# Shield_V4_Connector_test_only.net
KiCad netlist of a schematic drawn in EasyEDA
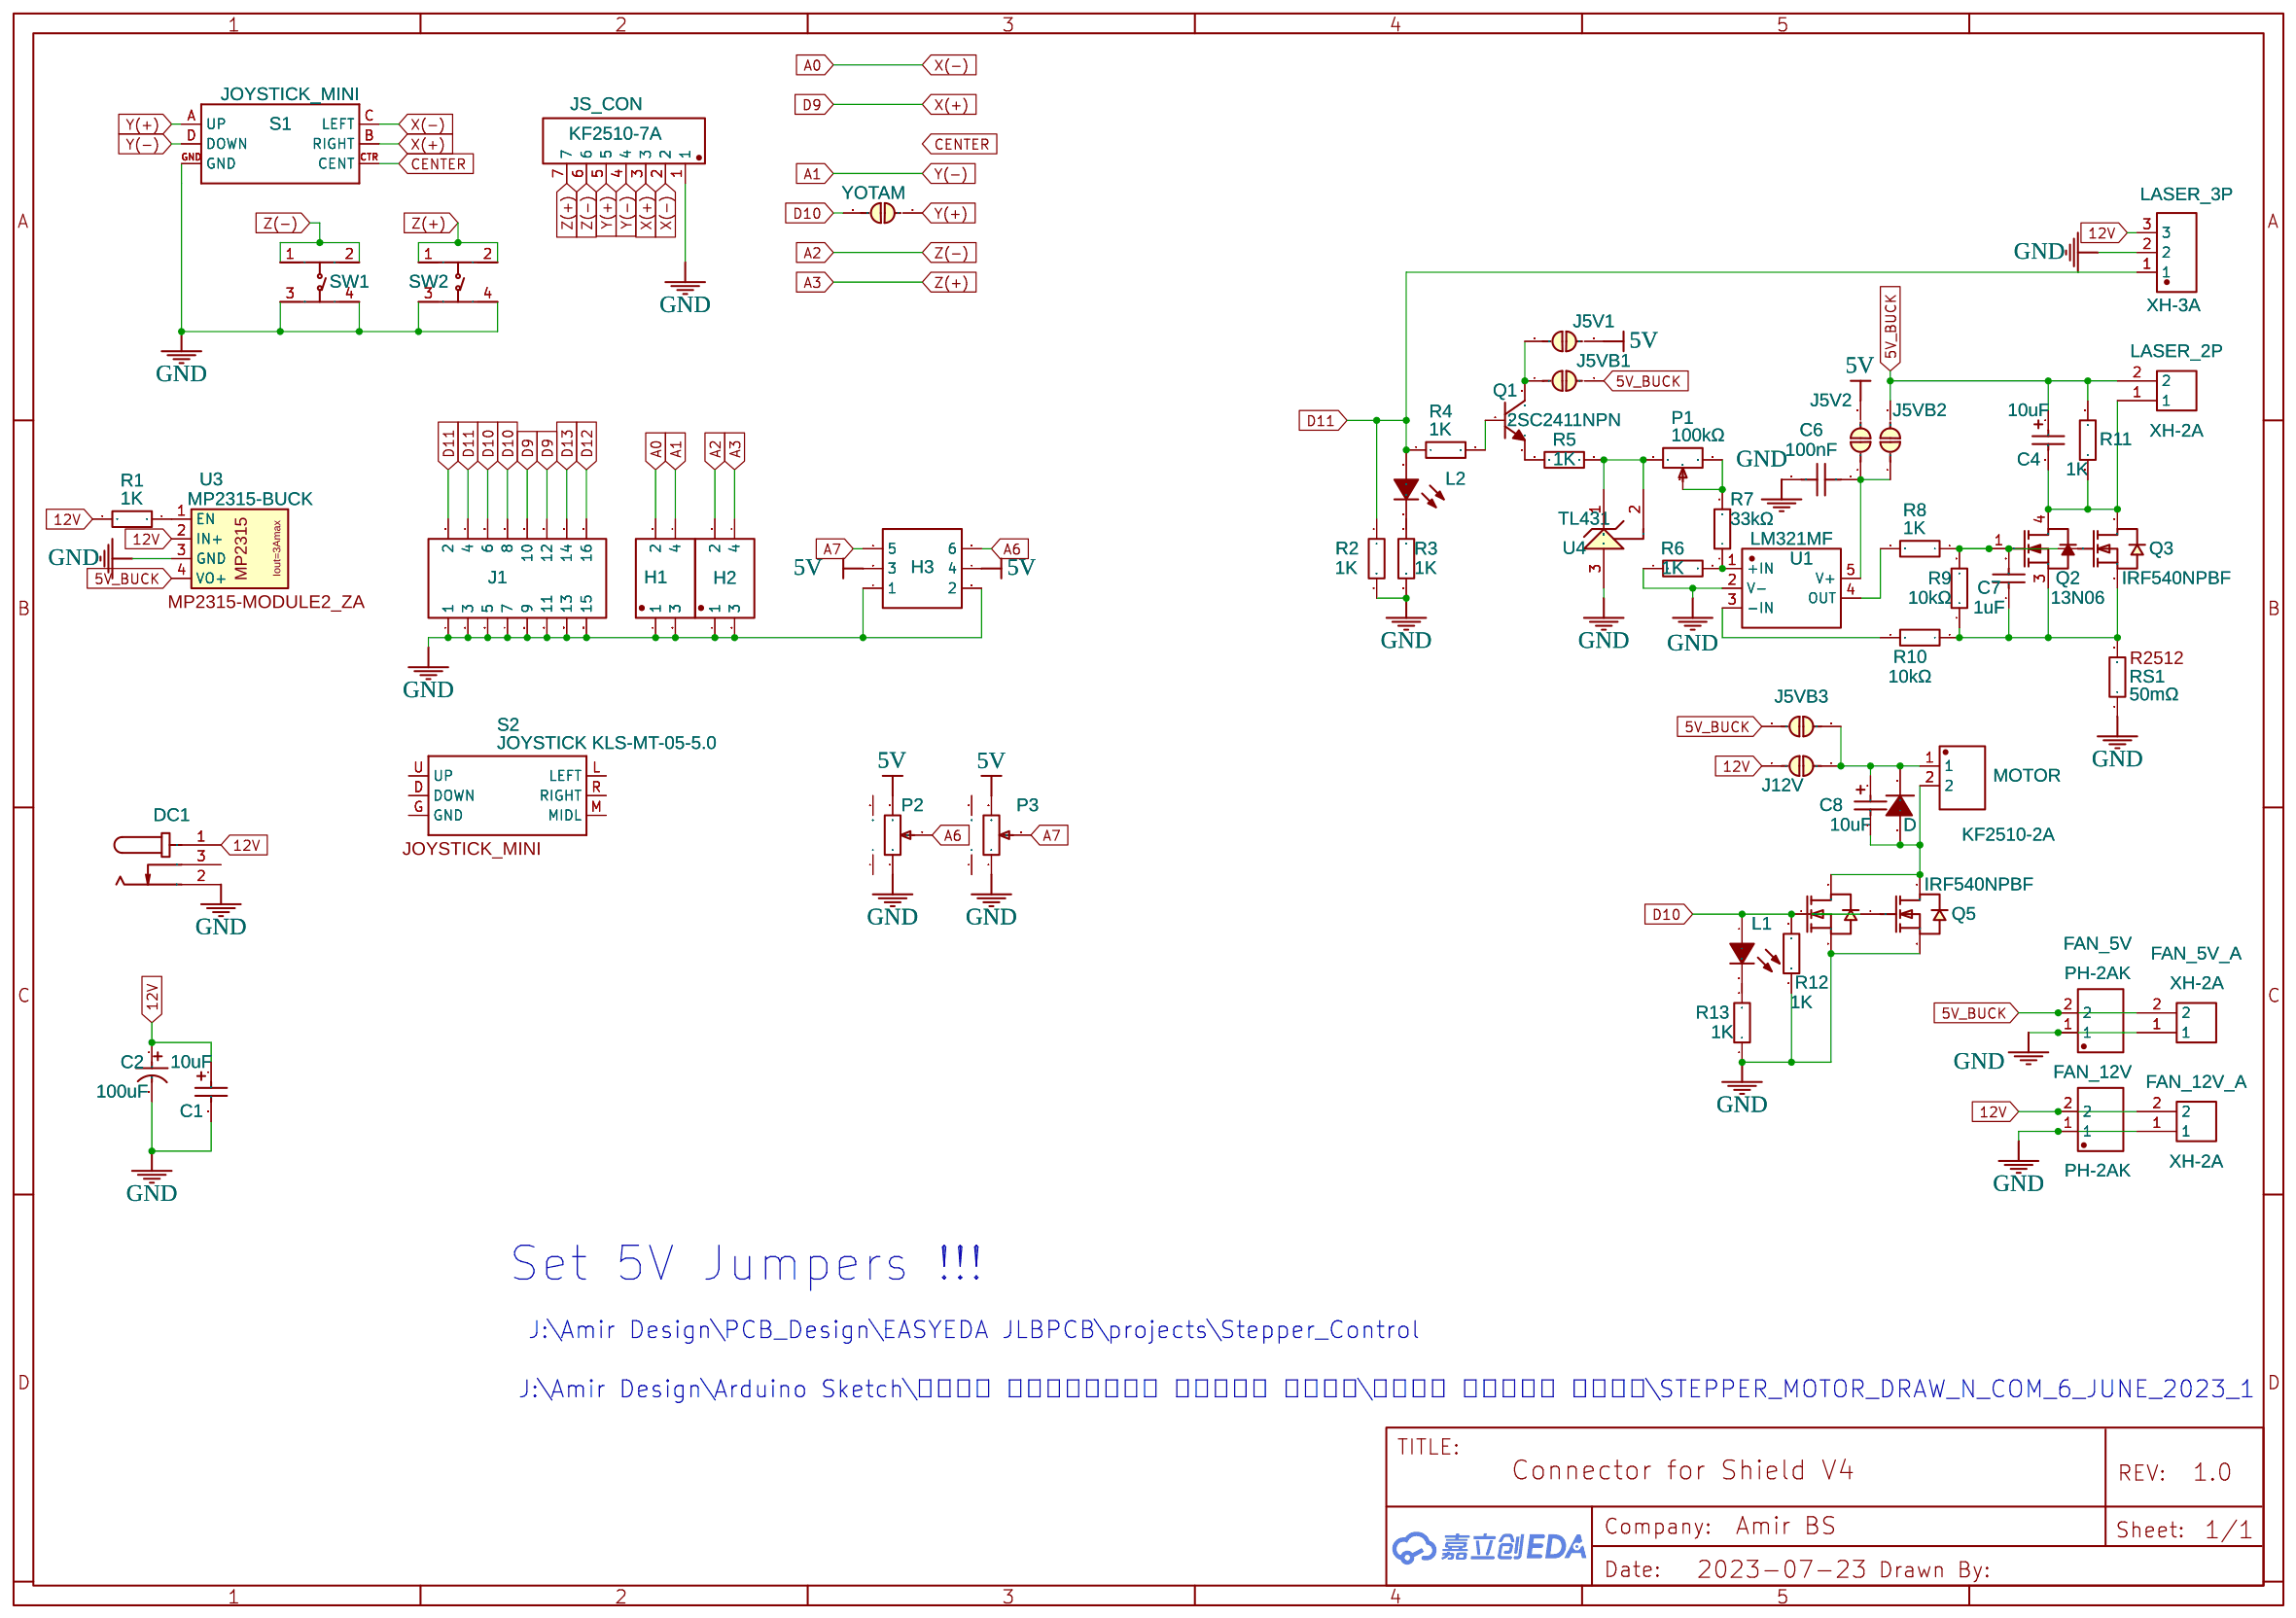
[diagram p0: schematic sheet]

(export (version "E")
  (design (tool "Eeschema 10.0.6"))
  (components
    (comp (ref "C1")
      (value "10uF")
      (fields (field (name "Manufacturer Part") "TAJA106K016RNJ") (field (name "Manufacturer") "Kyocera AVX"))
      (libsource (lib "") (part "TAJA106K016RNJ"))
    )
    (comp (ref "C2")
      (value "100uF")
      (fields
        (field (name "Manufacturer Part") "KM107M035E11RR0VH2FP0")
        (field (name "Manufacturer") "CX(承兴)")
      )
      (libsource (lib "") (part "100uF 35V 6.3*11"))
    )
    (comp (ref "C4")
      (value "10uF")
      (fields (field (name "Manufacturer Part") "TAJA106K016RNJ") (field (name "Manufacturer") "Kyocera AVX"))
      (libsource (lib "") (part "TAJA106K016RNJ"))
    )
    (comp (ref "C6")
      (value "100nF")
      (fields
        (field (name "BOM_Manufacturer Part") "CC0603KRX7R9BB104")
        (field (name "BOM_Supplier Part") "C14663")
      )
      (libsource (lib "") (part "CC0603KRX7R9BB104"))
    )
    (comp (ref "C7")
      (value "1uF")
      (fields
        (field (name "Manufacturer Part") "CL10A105KB8NNNC")
        (field (name "Manufacturer") "SAMSUNG(三星)")
      )
      (libsource (lib "") (part "CL10A105KB8NNNC"))
    )
    (comp (ref "C8")
      (value "10uF")
      (fields (field (name "Manufacturer Part") "TAJA106K016RNJ") (field (name "Manufacturer") "Kyocera AVX"))
      (libsource (lib "") (part "TAJA106K016RNJ"))
    )
    (comp (ref "D")
      (value "1N4007")
      (fields (field (name "BOM_Manufacturer Part") "1N4007F") (field (name "BOM_Supplier Part") "C110856"))
      (libsource (lib "") (part "1N4007F"))
    )
    (comp (ref "DC1")
      (value "DC")
      (fields
        (field (name "BOM_Manufacturer Part") "DC005-2.0MM")
        (field (name "BOM_Supplier Part") "C111567")
      )
      (libsource (lib "") (part "DC005-2.0MM"))
    )
    (comp (ref "FAN_5V")
      (value "PH-2AK")
      (fields (field (name "BOM_Supplier Part") "C8886"))
      (libsource (lib "") (part "PH-2AK"))
    )
    (comp (ref "FAN_5V_A")
      (value "XH-2A")
      (fields (field (name "Manufacturer") "BOOMELE(博穆精密)"))
      (libsource (lib "") (part "XH-2A_1"))
    )
    (comp (ref "FAN_12V")
      (value "PH-2AK")
      (fields (field (name "BOM_Supplier Part") "C8886"))
      (libsource (lib "") (part "PH-2AK_1"))
    )
    (comp (ref "FAN_12V_A")
      (value "XH-2A")
      (fields (field (name "Manufacturer") "BOOMELE(博穆精密)"))
      (libsource (lib "") (part "XH-2A"))
    )
    (comp (ref "H1")
      (value "Header-Female-2.54_2x2")
      (fields
        (field (name "BOM_Manufacturer Part") "DS1023-2*2SF11")
        (field (name "BOM_Supplier Part") "C92273")
      )
      (libsource (lib "") (part "Header-Female-2.54_2x2"))
    )
    (comp (ref "H2")
      (value "Header-Female-2.54_2x2")
      (fields
        (field (name "BOM_Manufacturer Part") "DS1023-2*2SF11")
        (field (name "BOM_Supplier Part") "C92273")
      )
      (libsource (lib "") (part "Header-Female-2.54_2x2"))
    )
    (comp (ref "H3")
      (value "Header-Female-2.54_2x3")
      (fields
        (field (name "BOM_Manufacturer Part") "DS1023-2*3SF11")
        (field (name "BOM_Supplier Part") "C92272")
      )
      (libsource (lib "") (part "Header-Female-2.54_2x3"))
    )
    (comp (ref "J1")
      (value "Header-Female-2.54_2x8")
      (fields (field (name "BOM_Manufacturer Part") "2.54-2*8P母") (field (name "BOM_Supplier Part") "C30734"))
      (libsource (lib "") (part "Header-Female-2.54_2x8"))
    )
    (comp (ref "J5V1") (value "JUMPER-SMT_2") (libsource (lib "") (part "JUMPER-SMT_2_2")))
    (comp (ref "J5V2") (value "JUMPER-SMT_2") (libsource (lib "") (part "JUMPER-SMT_2_5")))
    (comp (ref "J5VB1") (value "JUMPER-SMT_2") (libsource (lib "") (part "JUMPER-SMT_2_6")))
    (comp (ref "J5VB2") (value "JUMPER-SMT_2") (libsource (lib "") (part "JUMPER-SMT_2")))
    (comp (ref "J5VB3") (value "JUMPER-SMT_2") (libsource (lib "") (part "JUMPER-SMT_2_1")))
    (comp (ref "J12V") (value "JUMPER-SMT_2") (libsource (lib "") (part "JUMPER-SMT_2_4")))
    (comp (ref "JS_CON")
      (value "KF2510-7A")
      (fields (field (name "Manufacturer") "BOOMELE"))
      (libsource (lib "") (part "KF2510-7A"))
    )
    (comp (ref "L1")
      (value "LED")
      (fields
        (field (name "BOM_Manufacturer Part") "19-217/BHC-ZL1M2RY/3T")
        (field (name "BOM_Supplier Part") "C72041")
      )
      (libsource (lib "") (part "19-217/BHC-ZL1M2RY/3T"))
    )
    (comp (ref "L2")
      (value "LED")
      (fields
        (field (name "BOM_Manufacturer Part") "19-217/BHC-ZL1M2RY/3T")
        (field (name "BOM_Supplier Part") "C72041")
      )
      (libsource (lib "") (part "19-217/BHC-ZL1M2RY/3T"))
    )
    (comp (ref "LASER_2P")
      (value "XH-2A")
      (fields (field (name "Manufacturer") "BOOMELE(博穆精密)"))
      (libsource (lib "") (part "XH-2A_2"))
    )
    (comp (ref "LASER_3P")
      (value "XH-3A")
      (fields (field (name "Manufacturer") "HCTL(华灿天禄)"))
      (libsource (lib "") (part "XH-3A_C2908601"))
    )
    (comp (ref "MOTOR")
      (value "KF2510-2A")
      (fields (field (name "BOM_Supplier Part") "C27543"))
      (libsource (lib "") (part "KF2510-2A"))
    )
    (comp (ref "P1")
      (value "100kΩ")
      (fields (field (name "Manufacturer Part") "3296W-1-104LF") (field (name "Manufacturer") "BOURNS"))
      (libsource (lib "") (part "3296W-1-104LF"))
    )
    (comp (ref "P2")
      (value "长柄旋转电位器")
      (fields (field (name "BOM_Supplier Part") "C2874842"))
      (libsource (lib "") (part "长柄旋转电位器"))
    )
    (comp (ref "P3")
      (value "长柄旋转电位器")
      (fields (field (name "BOM_Supplier Part") "C2874842"))
      (libsource (lib "") (part "长柄旋转电位器"))
    )
    (comp (ref "Q1")
      (value "2SC2411NPN")
      (fields (field (name "Manufacturer Part") "2SC2411KT146R") (field (name "Manufacturer") "ROHM(罗姆)"))
      (libsource (lib "") (part "2SC2411KT146R"))
    )
    (comp (ref "Q2")
      (value "13N06")
      (fields (field (name "Manufacturer Part") "FQD13N06LTM") (field (name "Manufacturer") "onsemi(安森美)"))
      (libsource (lib "") (part "FQD13N06LTM"))
    )
    (comp (ref "Q3")
      (value "IRF540NPBF")
      (fields (field (name "Manufacturer") "Infineon(英飞凌)"))
      (libsource (lib "") (part "IRF540NPBF"))
    )
    (comp (ref "Q4")
      (value "Q")
      (fields (field (name "BOM_Manufacturer Part") "JSM2302") (field (name "BOM_Supplier Part") "C916403"))
      (libsource (lib "") (part "JSM2302"))
    )
    (comp (ref "Q5")
      (value "IRF540NPBF")
      (fields (field (name "Manufacturer") "Infineon(英飞凌)"))
      (libsource (lib "") (part "IRF540NPBF"))
    )
    (comp (ref "R1")
      (value "1K")
      (fields
        (field (name "BOM_Manufacturer Part") "0603WAF1001T5E")
        (field (name "BOM_Supplier Part") "C21190")
      )
      (libsource (lib "") (part "0603WAF1001T5E_2"))
    )
    (comp (ref "R2")
      (value "1K")
      (fields
        (field (name "BOM_Manufacturer Part") "0603WAF1001T5E")
        (field (name "BOM_Supplier Part") "C21190")
      )
      (libsource (lib "") (part "0603WAF1001T5E_3"))
    )
    (comp (ref "R3")
      (value "1K")
      (fields
        (field (name "BOM_Manufacturer Part") "0603WAF1001T5E")
        (field (name "BOM_Supplier Part") "C21190")
      )
      (libsource (lib "") (part "0603WAF1001T5E_3"))
    )
    (comp (ref "R4")
      (value "1K")
      (fields
        (field (name "BOM_Manufacturer Part") "0603WAF1001T5E")
        (field (name "BOM_Supplier Part") "C21190")
      )
      (libsource (lib "") (part "0603WAF1001T5E_1"))
    )
    (comp (ref "R5")
      (value "1K")
      (fields
        (field (name "BOM_Manufacturer Part") "0603WAF1001T5E")
        (field (name "BOM_Supplier Part") "C21190")
      )
      (libsource (lib "") (part "0603WAF1001T5E_2"))
    )
    (comp (ref "R6")
      (value "1K")
      (fields
        (field (name "BOM_Manufacturer Part") "0603WAF1001T5E")
        (field (name "BOM_Supplier Part") "C21190")
      )
      (libsource (lib "") (part "0603WAF1001T5E_1"))
    )
    (comp (ref "R7")
      (value "33kΩ")
      (fields
        (field (name "Manufacturer Part") "0603WAF3302T5E")
        (field (name "Manufacturer") "UNI-ROYAL(厚声)")
      )
      (libsource (lib "") (part "0603WAF3302T5E"))
    )
    (comp (ref "R8")
      (value "1K")
      (fields
        (field (name "BOM_Manufacturer Part") "0603WAF1001T5E")
        (field (name "BOM_Supplier Part") "C21190")
      )
      (libsource (lib "") (part "0603WAF1001T5E_2"))
    )
    (comp (ref "R9")
      (value "10kΩ")
      (fields
        (field (name "BOM_Manufacturer Part") "0603WAF1002T5E")
        (field (name "BOM_Supplier Part") "C25804")
      )
      (libsource (lib "") (part "0603WAF1002T5E"))
    )
    (comp (ref "R10")
      (value "10kΩ")
      (fields
        (field (name "BOM_Manufacturer Part") "0603WAF1002T5E")
        (field (name "BOM_Supplier Part") "C25804")
      )
      (libsource (lib "") (part "0603WAF1002T5E_1"))
    )
    (comp (ref "R11")
      (value "1K")
      (fields
        (field (name "BOM_Manufacturer Part") "0603WAF1001T5E")
        (field (name "BOM_Supplier Part") "C21190")
      )
      (libsource (lib "") (part "0603WAF1001T5E"))
    )
    (comp (ref "R12")
      (value "1K")
      (fields
        (field (name "BOM_Manufacturer Part") "0603WAF1001T5E")
        (field (name "BOM_Supplier Part") "C21190")
      )
      (libsource (lib "") (part "0603WAF1001T5E"))
    )
    (comp (ref "R13")
      (value "1K")
      (fields
        (field (name "BOM_Manufacturer Part") "0603WAF1001T5E")
        (field (name "BOM_Supplier Part") "C21190")
      )
      (libsource (lib "") (part "0603WAF1001T5E"))
    )
    (comp (ref "RS1")
      (value "50mΩ")
      (fields
        (field (name "Manufacturer Part") "CR2512FR050E04R")
        (field (name "Manufacturer") "EVER OHMS(天二科技)")
      )
      (libsource (lib "") (part "CR2512F0R05E04"))
    )
    (comp (ref "S1") (value "JOYSTICK_MINI") (libsource (lib "") (part "JOYSTICK_MINI")))
    (comp (ref "S2") (value "JOYSTICK KLS-MT-05-5.0") (libsource (lib "") (part "JOYSTICK KLS-MT-05-5.0")))
    (comp (ref "SW1")
      (value "TC-6610-7-160G")
      (fields (field (name "Manufacturer") "HCTL(华灿天禄)"))
      (libsource (lib "") (part "TC-6610-7-160G"))
    )
    (comp (ref "SW2")
      (value "TC-6610-7-160G")
      (fields (field (name "Manufacturer") "HCTL(华灿天禄)"))
      (libsource (lib "") (part "TC-6610-7-160G"))
    )
    (comp (ref "U1")
      (value "LM321MF")
      (fields (field (name "Manufacturer") "UMW(广东友台半导体)"))
      (libsource (lib "") (part "LM321MF"))
    )
    (comp (ref "U3") (value "MP2315-BUCK") (libsource (lib "") (part "MP2315-BUCK")))
    (comp (ref "U4")
      (value "TL431")
      (fields (field (name "Manufacturer Part") "TL431BIDBZR") (field (name "Manufacturer") "TI(德州仪器)"))
      (libsource (lib "") (part "TL431BIDBZR"))
    )
    (comp (ref "YOTAM") (value "JUMPER-SMT_2") (libsource (lib "") (part "JUMPER-SMT_2_3")))
  )
  (nets
    (net (code "1") (name "5V") (class "Default")
      (node (ref "H3") (pin "3") (pinfunction "3_3") (pintype "input"))
      (node (ref "H3") (pin "4") (pinfunction "4_4") (pintype "input"))
      (node (ref "J5V1") (pin "2") (pinfunction "2_2") (pintype "bidirectional"))
      (node (ref "J5V2") (pin "2") (pinfunction "2_2") (pintype "bidirectional"))
      (node (ref "P2") (pin "3") (pinfunction "3_3") (pintype "input"))
      (node (ref "P3") (pin "3") (pinfunction "3_3") (pintype "input"))
    )
    (net (code "2") (name "5V_BUCK") (class "Default")
      (node (ref "C4") (pin "1") (pinfunction "1_1") (pintype "input"))
      (node (ref "FAN_5V") (pin "2") (pinfunction "2_2") (pintype "unspecified"))
      (node (ref "FAN_5V_A") (pin "2") (pinfunction "2_2") (pintype "unspecified"))
      (node (ref "J5VB1") (pin "2") (pinfunction "2_2") (pintype "bidirectional"))
      (node (ref "J5VB2") (pin "2") (pinfunction "2_2") (pintype "bidirectional"))
      (node (ref "J5VB3") (pin "2") (pinfunction "2_2") (pintype "bidirectional"))
      (node (ref "LASER_2P") (pin "2") (pinfunction "2_2") (pintype "unspecified"))
      (node (ref "R11") (pin "2") (pinfunction "2_2") (pintype "input"))
      (node (ref "U3") (pin "4") (pinfunction "VO+_4") (pintype "unspecified"))
    )
    (net (code "3") (name "12V") (class "Default")
      (node (ref "C1") (pin "1") (pinfunction "1_1") (pintype "input"))
      (node (ref "C2") (pin "1") (pinfunction "1_1") (pintype "input"))
      (node (ref "DC1") (pin "1") (pinfunction "1_1") (pintype "unspecified"))
      (node (ref "FAN_12V") (pin "2") (pinfunction "2_2") (pintype "unspecified"))
      (node (ref "FAN_12V_A") (pin "2") (pinfunction "2_2") (pintype "unspecified"))
      (node (ref "J12V") (pin "2") (pinfunction "2_2") (pintype "bidirectional"))
      (node (ref "LASER_3P") (pin "3") (pinfunction "3_3") (pintype "unspecified"))
      (node (ref "R1") (pin "2") (pinfunction "2_2") (pintype "input"))
      (node (ref "U3") (pin "2") (pinfunction "IN+_2") (pintype "unspecified"))
    )
    (net (code "4") (name "A0") (class "Default")
      (node (ref "H1") (pin "2") (pinfunction "2_2") (pintype "unspecified"))
      (node (ref "JS_CON") (pin "2") (pinfunction "2_2") (pintype "unspecified"))
      (node (ref "S1") (pin "C") (pinfunction "LEFT_C") (pintype "unspecified"))
    )
    (net (code "5") (name "A1") (class "Default")
      (node (ref "H1") (pin "4") (pinfunction "4_4") (pintype "unspecified"))
      (node (ref "JS_CON") (pin "4") (pinfunction "4_4") (pintype "unspecified"))
      (node (ref "S1") (pin "D") (pinfunction "DOWN_D") (pintype "unspecified"))
    )
    (net (code "6") (name "A2") (class "Default")
      (node (ref "H2") (pin "2") (pinfunction "2_2") (pintype "unspecified"))
      (node (ref "JS_CON") (pin "6") (pinfunction "6_6") (pintype "unspecified"))
      (node (ref "SW1") (pin "1") (pinfunction "1_1") (pintype "unspecified"))
      (node (ref "SW1") (pin "2") (pinfunction "2_2") (pintype "unspecified"))
    )
    (net (code "7") (name "A3") (class "Default")
      (node (ref "H2") (pin "4") (pinfunction "4_4") (pintype "unspecified"))
      (node (ref "JS_CON") (pin "7") (pinfunction "7_7") (pintype "unspecified"))
      (node (ref "SW2") (pin "1") (pinfunction "1_1") (pintype "unspecified"))
      (node (ref "SW2") (pin "2") (pinfunction "2_2") (pintype "unspecified"))
    )
    (net (code "8") (name "A6") (class "Default")
      (node (ref "H3") (pin "6") (pinfunction "6_6") (pintype "input"))
      (node (ref "P2") (pin "2") (pinfunction "2_2") (pintype "input"))
    )
    (net (code "9") (name "A7") (class "Default")
      (node (ref "H3") (pin "5") (pinfunction "5_5") (pintype "input"))
      (node (ref "P3") (pin "2") (pinfunction "2_2") (pintype "input"))
    )
    (net (code "10") (name "CENTER") (class "Default")
      (node (ref "S1") (pin "CTR") (pinfunction "CENT_CTR") (pintype "unspecified"))
    )
    (net (code "11") (name "D9") (class "Default")
      (node (ref "J1") (pin "10") (pinfunction "10_10") (pintype "input"))
      (node (ref "J1") (pin "12") (pinfunction "12_12") (pintype "input"))
      (node (ref "JS_CON") (pin "3") (pinfunction "3_3") (pintype "unspecified"))
      (node (ref "S1") (pin "B") (pinfunction "RIGHT_B") (pintype "unspecified"))
    )
    (net (code "12") (name "D10") (class "Default")
      (node (ref "J1") (pin "6") (pinfunction "6_6") (pintype "input"))
      (node (ref "J1") (pin "8") (pinfunction "8_8") (pintype "input"))
      (node (ref "L1") (pin "1") (pinfunction "A_1") (pintype "input"))
      (node (ref "Q4") (pin "1") (pinfunction "G_1") (pintype "unspecified"))
      (node (ref "Q5") (pin "1") (pinfunction "G_1") (pintype "unspecified"))
      (node (ref "R12") (pin "2") (pinfunction "2_2") (pintype "input"))
      (node (ref "YOTAM") (pin "1") (pinfunction "1_1") (pintype "bidirectional"))
    )
    (net (code "13") (name "D11") (class "Default")
      (node (ref "J1") (pin "2") (pinfunction "2_2") (pintype "input"))
      (node (ref "J1") (pin "4") (pinfunction "4_4") (pintype "input"))
      (node (ref "L2") (pin "1") (pinfunction "A_1") (pintype "input"))
      (node (ref "LASER_3P") (pin "1") (pinfunction "1_1") (pintype "unspecified"))
      (node (ref "R2") (pin "1") (pinfunction "1_1") (pintype "input"))
      (node (ref "R4") (pin "1") (pinfunction "1_1") (pintype "input"))
    )
    (net (code "14") (name "D12") (class "Default")
      (node (ref "J1") (pin "16") (pinfunction "16_16") (pintype "input"))
    )
    (net (code "15") (name "D13") (class "Default")
      (node (ref "J1") (pin "14") (pinfunction "14_14") (pintype "input"))
    )
    (net (code "16") (name "GND") (class "Default")
      (node (ref "C1") (pin "2") (pinfunction "2_2") (pintype "input"))
      (node (ref "C2") (pin "2") (pinfunction "2_2") (pintype "input"))
      (node (ref "C6") (pin "2") (pinfunction "2_2") (pintype "unspecified"))
      (node (ref "DC1") (pin "2") (pinfunction "2_2") (pintype "unspecified"))
      (node (ref "FAN_12V") (pin "1") (pinfunction "1_1") (pintype "unspecified"))
      (node (ref "FAN_12V_A") (pin "1") (pinfunction "1_1") (pintype "unspecified"))
      (node (ref "FAN_5V") (pin "1") (pinfunction "1_1") (pintype "unspecified"))
      (node (ref "FAN_5V_A") (pin "1") (pinfunction "1_1") (pintype "unspecified"))
      (node (ref "H1") (pin "1") (pinfunction "1_1") (pintype "unspecified"))
      (node (ref "H1") (pin "3") (pinfunction "3_3") (pintype "unspecified"))
      (node (ref "H2") (pin "1") (pinfunction "1_1") (pintype "unspecified"))
      (node (ref "H2") (pin "3") (pinfunction "3_3") (pintype "unspecified"))
      (node (ref "H3") (pin "1") (pinfunction "1_1") (pintype "input"))
      (node (ref "H3") (pin "2") (pinfunction "2_2") (pintype "input"))
      (node (ref "J1") (pin "1") (pinfunction "1_1") (pintype "input"))
      (node (ref "J1") (pin "11") (pinfunction "11_11") (pintype "input"))
      (node (ref "J1") (pin "13") (pinfunction "13_13") (pintype "input"))
      (node (ref "J1") (pin "15") (pinfunction "15_15") (pintype "input"))
      (node (ref "J1") (pin "3") (pinfunction "3_3") (pintype "input"))
      (node (ref "J1") (pin "5") (pinfunction "5_5") (pintype "input"))
      (node (ref "J1") (pin "7") (pinfunction "7_7") (pintype "input"))
      (node (ref "J1") (pin "9") (pinfunction "9_9") (pintype "input"))
      (node (ref "JS_CON") (pin "1") (pinfunction "1_1") (pintype "unspecified"))
      (node (ref "LASER_3P") (pin "2") (pinfunction "2_2") (pintype "unspecified"))
      (node (ref "P2") (pin "1") (pinfunction "1_1") (pintype "input"))
      (node (ref "P3") (pin "1") (pinfunction "1_1") (pintype "input"))
      (node (ref "Q4") (pin "2") (pinfunction "S_2") (pintype "unspecified"))
      (node (ref "Q5") (pin "3") (pinfunction "S_3") (pintype "unspecified"))
      (node (ref "R12") (pin "1") (pinfunction "1_1") (pintype "input"))
      (node (ref "R13") (pin "1") (pinfunction "1_1") (pintype "input"))
      (node (ref "R2") (pin "2") (pinfunction "2_2") (pintype "input"))
      (node (ref "R3") (pin "2") (pinfunction "2_2") (pintype "input"))
      (node (ref "R6") (pin "1") (pinfunction "1_1") (pintype "input"))
      (node (ref "RS1") (pin "1") (pinfunction "1_1") (pintype "unspecified"))
      (node (ref "S1") (pin "GND") (pinfunction "GND_GND") (pintype "unspecified"))
      (node (ref "SW1") (pin "3") (pinfunction "3_3") (pintype "unspecified"))
      (node (ref "SW1") (pin "4") (pinfunction "4_4") (pintype "unspecified"))
      (node (ref "SW2") (pin "3") (pinfunction "3_3") (pintype "unspecified"))
      (node (ref "SW2") (pin "4") (pinfunction "4_4") (pintype "unspecified"))
      (node (ref "U1") (pin "2") (pinfunction "V-_2") (pintype "unspecified"))
      (node (ref "U3") (pin "3") (pinfunction "GND_3") (pintype "unspecified"))
      (node (ref "U4") (pin "3") (pinfunction "ANODE_3") (pintype "unspecified"))
    )
    (net (code "17") (name "Net-(D-A)") (class "Default")
      (node (ref "C8") (pin "2") (pinfunction "2_2") (pintype "input"))
      (node (ref "D") (pin "2") (pinfunction "A_2") (pintype "unspecified"))
      (node (ref "MOTOR") (pin "2") (pinfunction "2_2") (pintype "unspecified"))
      (node (ref "Q4") (pin "3") (pinfunction "D_3") (pintype "unspecified"))
      (node (ref "Q5") (pin "2") (pinfunction "D_2") (pintype "unspecified"))
    )
    (net (code "18") (name "Net-(D-C)") (class "Default")
      (node (ref "C8") (pin "1") (pinfunction "1_1") (pintype "input"))
      (node (ref "D") (pin "1") (pinfunction "C_1") (pintype "unspecified"))
      (node (ref "J12V") (pin "1") (pinfunction "1_1") (pintype "bidirectional"))
      (node (ref "J5VB3") (pin "1") (pinfunction "1_1") (pintype "bidirectional"))
      (node (ref "MOTOR") (pin "1") (pinfunction "1_1") (pintype "unspecified"))
    )
    (net (code "19") (name "Net-(L1-C)") (class "Default")
      (node (ref "L1") (pin "2") (pinfunction "C_2") (pintype "input"))
      (node (ref "R13") (pin "2") (pinfunction "2_2") (pintype "input"))
    )
    (net (code "20") (name "Net-(L2-C)") (class "Default")
      (node (ref "L2") (pin "2") (pinfunction "C_2") (pintype "input"))
      (node (ref "R3") (pin "1") (pinfunction "1_1") (pintype "input"))
    )
    (net (code "21") (name "Net-(P1-Pad2)") (class "Default")
      (node (ref "P1") (pin "2") (pinfunction "2_2") (pintype "input"))
      (node (ref "P1") (pin "3") (pinfunction "3_3") (pintype "input"))
      (node (ref "R7") (pin "2") (pinfunction "2_2") (pintype "input"))
    )
    (net (code "22") (name "Net-(Q1-B)") (class "Default")
      (node (ref "Q1") (pin "2") (pinfunction "B_2") (pintype "unspecified"))
      (node (ref "R4") (pin "2") (pinfunction "2_2") (pintype "input"))
    )
    (net (code "23") (name "Net-(Q1-C)") (class "Default")
      (node (ref "J5V1") (pin "1") (pinfunction "1_1") (pintype "bidirectional"))
      (node (ref "J5VB1") (pin "1") (pinfunction "1_1") (pintype "bidirectional"))
      (node (ref "Q1") (pin "3") (pinfunction "C_3") (pintype "unspecified"))
    )
    (net (code "24") (name "Net-(Q1-E)") (class "Default")
      (node (ref "Q1") (pin "1") (pinfunction "E_1") (pintype "unspecified"))
      (node (ref "R5") (pin "2") (pinfunction "2_2") (pintype "input"))
    )
    (net (code "25") (name "Net-(Q2-D)") (class "Default")
      (node (ref "C4") (pin "2") (pinfunction "2_2") (pintype "input"))
      (node (ref "LASER_2P") (pin "1") (pinfunction "1_1") (pintype "unspecified"))
      (node (ref "Q2") (pin "4") (pinfunction "D_4") (pintype "unspecified"))
      (node (ref "Q3") (pin "2") (pinfunction "D_2") (pintype "unspecified"))
      (node (ref "R11") (pin "1") (pinfunction "1_1") (pintype "input"))
    )
    (net (code "26") (name "Net-(Q2-G)") (class "Default")
      (node (ref "C7") (pin "2") (pinfunction "2_2") (pintype "input"))
      (node (ref "Q2") (pin "1") (pinfunction "G_1") (pintype "unspecified"))
      (node (ref "Q3") (pin "1") (pinfunction "G_1") (pintype "unspecified"))
      (node (ref "R8") (pin "1") (pinfunction "1_1") (pintype "input"))
      (node (ref "R9") (pin "2") (pinfunction "2_2") (pintype "input"))
    )
    (net (code "27") (name "Net-(Q2-S)") (class "Default")
      (node (ref "C7") (pin "1") (pinfunction "1_1") (pintype "input"))
      (node (ref "Q2") (pin "3") (pinfunction "S_3") (pintype "unspecified"))
      (node (ref "Q3") (pin "3") (pinfunction "S_3") (pintype "unspecified"))
      (node (ref "R10") (pin "1") (pinfunction "1_1") (pintype "input"))
      (node (ref "R9") (pin "1") (pinfunction "1_1") (pintype "input"))
      (node (ref "RS1") (pin "2") (pinfunction "2_2") (pintype "unspecified"))
    )
    (net (code "28") (name "Net-(U1-+IN)") (class "Default")
      (node (ref "R6") (pin "2") (pinfunction "2_2") (pintype "input"))
      (node (ref "R7") (pin "1") (pinfunction "1_1") (pintype "input"))
      (node (ref "U1") (pin "1") (pinfunction "+IN_1") (pintype "unspecified"))
    )
    (net (code "29") (name "Net-(U1--IN)") (class "Default")
      (node (ref "R10") (pin "2") (pinfunction "2_2") (pintype "input"))
      (node (ref "U1") (pin "3") (pinfunction "-IN_3") (pintype "unspecified"))
    )
    (net (code "30") (name "Net-(U1-OUT)") (class "Default")
      (node (ref "R8") (pin "2") (pinfunction "2_2") (pintype "input"))
      (node (ref "U1") (pin "4") (pinfunction "OUT_4") (pintype "unspecified"))
    )
    (net (code "31") (name "Net-(U1-V+)") (class "Default")
      (node (ref "C6") (pin "1") (pinfunction "1_1") (pintype "unspecified"))
      (node (ref "J5V2") (pin "1") (pinfunction "1_1") (pintype "bidirectional"))
      (node (ref "J5VB2") (pin "1") (pinfunction "1_1") (pintype "bidirectional"))
      (node (ref "U1") (pin "5") (pinfunction "V+_5") (pintype "unspecified"))
    )
    (net (code "32") (name "Net-(U3-EN)") (class "Default")
      (node (ref "R1") (pin "1") (pinfunction "1_1") (pintype "input"))
      (node (ref "U3") (pin "1") (pinfunction "EN_1") (pintype "unspecified"))
    )
    (net (code "33") (name "Net-(U4-CATHODE)") (class "Default")
      (node (ref "P1") (pin "1") (pinfunction "1_1") (pintype "input"))
      (node (ref "R5") (pin "1") (pinfunction "1_1") (pintype "input"))
      (node (ref "U4") (pin "1") (pinfunction "CATHODE_1") (pintype "unspecified"))
      (node (ref "U4") (pin "2") (pinfunction "REF_2") (pintype "unspecified"))
    )
    (net (code "34") (name "Y(+)") (class "Default")
      (node (ref "JS_CON") (pin "5") (pinfunction "5_5") (pintype "unspecified"))
      (node (ref "S1") (pin "A") (pinfunction "UP_A") (pintype "unspecified"))
      (node (ref "YOTAM") (pin "2") (pinfunction "2_2") (pintype "bidirectional"))
    )
    (net (code "35") (name "unconnected-(DC1-Pad3)") (class "Default")
      (node (ref "DC1") (pin "3") (pinfunction "3_3") (pintype "unspecified"))
    )
    (net (code "36") (name "unconnected-(P2-Pad4)") (class "Default")
      (node (ref "P2") (pin "4") (pinfunction "4_4") (pintype "input"))
    )
    (net (code "37") (name "unconnected-(P2-Pad5)") (class "Default")
      (node (ref "P2") (pin "5") (pinfunction "5_5") (pintype "input"))
    )
    (net (code "38") (name "unconnected-(P3-Pad4)") (class "Default")
      (node (ref "P3") (pin "4") (pinfunction "4_4") (pintype "input"))
    )
    (net (code "39") (name "unconnected-(P3-Pad5)") (class "Default")
      (node (ref "P3") (pin "5") (pinfunction "5_5") (pintype "input"))
    )
    (net (code "40") (name "unconnected-(S2-DOWN-PadD)") (class "Default")
      (node (ref "S2") (pin "D") (pinfunction "DOWN_D") (pintype "unspecified"))
    )
    (net (code "41") (name "unconnected-(S2-GND-PadG)") (class "Default")
      (node (ref "S2") (pin "G") (pinfunction "GND_G") (pintype "unspecified"))
    )
    (net (code "42") (name "unconnected-(S2-LEFT-PadL)") (class "Default")
      (node (ref "S2") (pin "L") (pinfunction "LEFT_L") (pintype "unspecified"))
    )
    (net (code "43") (name "unconnected-(S2-MIDL-PadM)") (class "Default")
      (node (ref "S2") (pin "M") (pinfunction "MIDL_M") (pintype "unspecified"))
    )
    (net (code "44") (name "unconnected-(S2-RIGHT-PadR)") (class "Default")
      (node (ref "S2") (pin "R") (pinfunction "RIGHT_R") (pintype "unspecified"))
    )
    (net (code "45") (name "unconnected-(S2-UP-PadU)") (class "Default")
      (node (ref "S2") (pin "U") (pinfunction "UP_U") (pintype "unspecified"))
    )
  )
)
